# Power_driver_MCU.net
KiCad netlist of a schematic drawn in Altium Designer
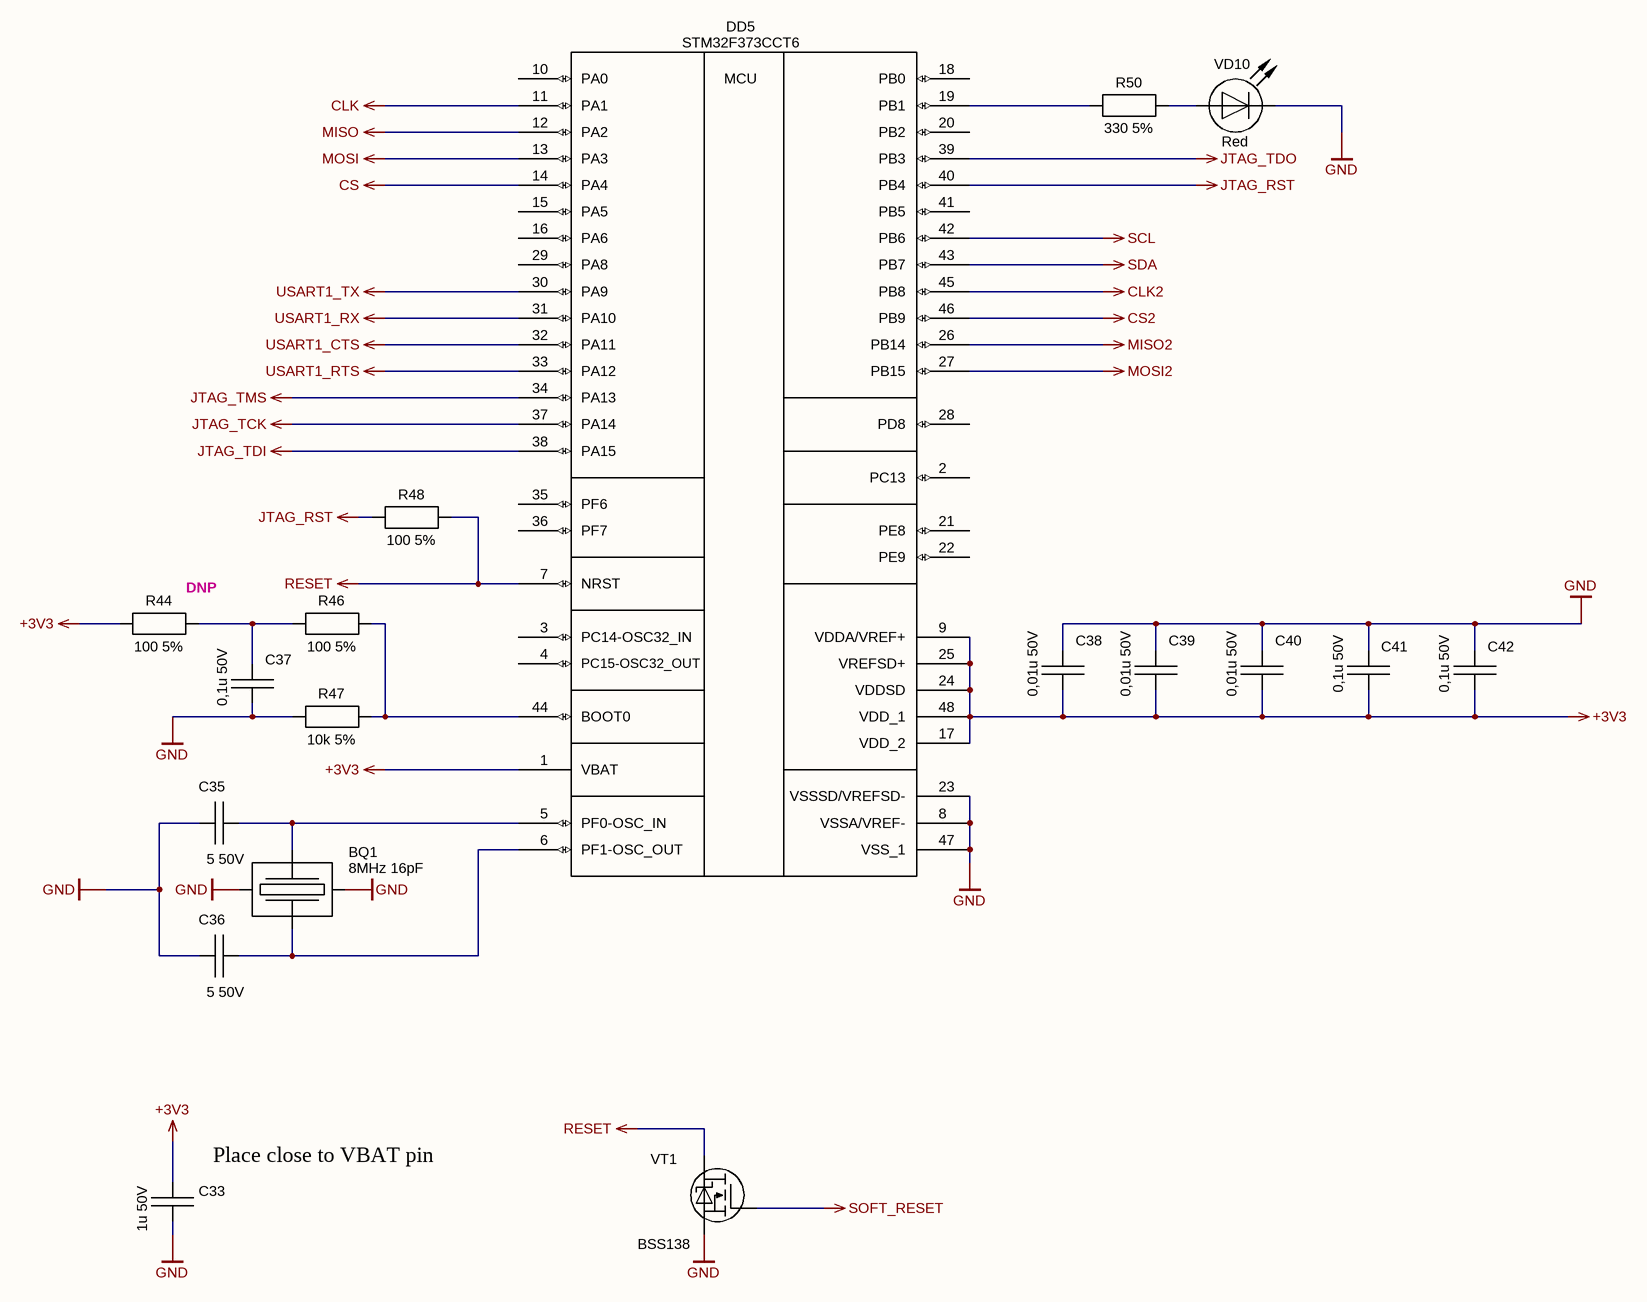
[diagram p0: Power_driver_MCU.SchDoc]

(export (version "E")
  (design (tool "Eeschema 10.0.6"))
  (components
    (comp (ref "BQ1")
      (value "8MHz 16pF")
      (footprint "Crystal_50x32x110")
      (description "Резонатор кварцевый 8 МГц, 50 ppm, 16 пФ, 5,0 x 3,2mm, SMT")
      (fields
        (field (name "PARTNUMBER") "KX-9A 8.0 MHz")
        (field (name "MANUFACTURER") "Geyer")
        (field (name "DESIGNER") "Pashinskiy")
      )
      (libsource (lib "RQCLib") (part "Crystal_4_pins"))
    )
    (comp (ref "C33")
      (value "1u 50V")
      (footprint "C0603_CAPC1608X09N")
      (description "Конденсатор керамический (MLCC) общего назначения 0603")
      (fields
        (field (name "PARTNUMBER") "CC0603KRX7R9BB105")
        (field (name "MANUFACTURER") "YAGEO")
        (field (name "DESIGNER") "Dudarev")
      )
      (libsource (lib "RQCLib") (part "Capacitor"))
    )
    (comp (ref "C35")
      (value "5 50V")
      (footprint "C0603_CAPC1608X09N")
      (description "Конденсатор керамический (MLCC) общего назначения 0603")
      (fields
        (field (name "PARTNUMBER") "CC0603CRNPO9BN5R0")
        (field (name "MANUFACTURER") "YAGEO")
        (field (name "DESIGNER") "Pashinskiy")
      )
      (libsource (lib "RQCLib") (part "Capacitor"))
    )
    (comp (ref "C36")
      (value "5 50V")
      (footprint "C0603_CAPC1608X09N")
      (description "Конденсатор керамический (MLCC) общего назначения 0603")
      (fields
        (field (name "PARTNUMBER") "CC0603CRNPO9BN5R0")
        (field (name "MANUFACTURER") "YAGEO")
        (field (name "DESIGNER") "Pashinskiy")
      )
      (libsource (lib "RQCLib") (part "Capacitor"))
    )
    (comp (ref "C37")
      (value "0,1u 50V")
      (footprint "C0603_CAPC1608X09N")
      (description "Конденсатор керамический (MLCC) общего назначения 0603")
      (fields
        (field (name "PARTNUMBER") "CC0603KRX7R9BB104")
        (field (name "MANUFACTURER") "YAGEO")
        (field (name "DESIGNER") "Dudarev")
      )
      (libsource (lib "RQCLib") (part "Capacitor"))
    )
    (comp (ref "C38")
      (value "0,01u 50V")
      (footprint "C0603_CAPC1608X09N")
      (description "Конденсатор керамический (MLCC) общего назначения 0603")
      (fields
        (field (name "PARTNUMBER") "CC0603KRX7R9BB103")
        (field (name "MANUFACTURER") "YAGEO")
        (field (name "DESIGNER") "Dudarev")
      )
      (libsource (lib "RQCLib") (part "Capacitor"))
    )
    (comp (ref "C39")
      (value "0,01u 50V")
      (footprint "C0603_CAPC1608X09N")
      (description "Конденсатор керамический (MLCC) общего назначения 0603")
      (fields
        (field (name "PARTNUMBER") "CC0603KRX7R9BB103")
        (field (name "MANUFACTURER") "YAGEO")
        (field (name "DESIGNER") "Dudarev")
      )
      (libsource (lib "RQCLib") (part "Capacitor"))
    )
    (comp (ref "C40")
      (value "0,01u 50V")
      (footprint "C0603_CAPC1608X09N")
      (description "Конденсатор керамический (MLCC) общего назначения 0603")
      (fields
        (field (name "PARTNUMBER") "CC0603KRX7R9BB103")
        (field (name "MANUFACTURER") "YAGEO")
        (field (name "DESIGNER") "Dudarev")
      )
      (libsource (lib "RQCLib") (part "Capacitor"))
    )
    (comp (ref "C41")
      (value "0,1u 50V")
      (footprint "C0603_CAPC1608X09N")
      (description "Конденсатор керамический (MLCC) общего назначения 0603")
      (fields
        (field (name "PARTNUMBER") "CC0603KRX7R9BB104")
        (field (name "MANUFACTURER") "YAGEO")
        (field (name "DESIGNER") "Dudarev")
      )
      (libsource (lib "RQCLib") (part "Capacitor"))
    )
    (comp (ref "C42")
      (value "0,1u 50V")
      (footprint "C0603_CAPC1608X09N")
      (description "Конденсатор керамический (MLCC) общего назначения 0603")
      (fields
        (field (name "PARTNUMBER") "CC0603KRX7R9BB104")
        (field (name "MANUFACTURER") "YAGEO")
        (field (name "DESIGNER") "Dudarev")
      )
      (libsource (lib "RQCLib") (part "Capacitor"))
    )
    (comp (ref "DD5")
      (value "STM32F373CCT6")
      (footprint "LQFP48_TSQFP50P900X900X160-48L")
      (description "Microcontroller ARM Cortex-M4, 32b, MCU+FPU, 1,25DMIPS, 256 kB Flash, 32kB SRAM, USB, LQFP48")
      (libsource (lib "IC_Controller") (part "STM32F373CCT6"))
    )
    (comp (ref "R44")
      (value "100 5%")
      (footprint "R0603_RESC1608X06N")
      (description "Резистор толстопленочный общего назначения 0603")
      (fields
        (field (name "PARTNUMBER") "RC0603JR-07100RL")
        (field (name "STAFF") "DNP")
        (field (name "MANUFACTURER") "YAGEO")
        (field (name "DESIGNER") "Dudarev")
      )
      (libsource (lib "RQCLib") (part "Resistor"))
    )
    (comp (ref "R46")
      (value "100 5%")
      (footprint "R0603_RESC1608X06N")
      (description "Резистор толстопленочный общего назначения 0603")
      (fields
        (field (name "PARTNUMBER") "RC0603JR-07100RL")
        (field (name "MANUFACTURER") "YAGEO")
        (field (name "DESIGNER") "Dudarev")
      )
      (libsource (lib "RQCLib") (part "Resistor"))
    )
    (comp (ref "R47")
      (value "10k 5%")
      (footprint "R0603_RESC1608X06N")
      (description "Резистор толстопленочный общего назначения 0603")
      (fields
        (field (name "PARTNUMBER") "RC0603JR-0710KL")
        (field (name "MANUFACTURER") "YAGEO")
        (field (name "DESIGNER") "Dudarev")
      )
      (libsource (lib "RQCLib") (part "Resistor"))
    )
    (comp (ref "R48")
      (value "100 5%")
      (footprint "R0603_RESC1608X06N")
      (description "Резистор толстопленочный общего назначения 0603")
      (fields
        (field (name "PARTNUMBER") "RC0603JR-07100RL")
        (field (name "MANUFACTURER") "YAGEO")
        (field (name "DESIGNER") "Dudarev")
      )
      (libsource (lib "RQCLib") (part "Resistor"))
    )
    (comp (ref "R50")
      (value "330 5%")
      (footprint "R0603_RESC1608X06N")
      (description "Резистор толстопленочный общего назначения 0603")
      (fields
        (field (name "PARTNUMBER") "RC0603JR-07330RL")
        (field (name "MANUFACTURER") "YAGEO")
        (field (name "DESIGNER") "Dudarev")
      )
      (libsource (lib "RQCLib") (part "Resistor"))
    )
    (comp (ref "VD10")
      (value "Red")
      (footprint "LED_0603")
      (description "LED SMD Super Red 1,6mm x 0,8mm")
      (fields
        (field (name "PARTNUMBER") "VLMS1300-GS08")
        (field (name "MANUFACTURER") "Vishay Semiconductors")
        (field (name "DESIGNER") "Losev")
      )
      (libsource (lib "RQCLib") (part "LED"))
    )
    (comp (ref "VT1")
      (value "BSS138")
      (footprint "SOT23_SOT95P237X110-3M")
      (description "N-Channel MOSFET transistor Logic level")
      (libsource (lib "Discrete") (part "N-MOSFET"))
    )
  )
  (nets
    (net (code "1") (name "+3V3") (class "Default")
      (node (ref "C33") (pin "2") (pinfunction "2_2") (pintype "passive"))
      (node (ref "C38") (pin "2") (pinfunction "2_2") (pintype "passive"))
      (node (ref "C39") (pin "2") (pinfunction "2_2") (pintype "passive"))
      (node (ref "C40") (pin "2") (pinfunction "2_2") (pintype "passive"))
      (node (ref "C41") (pin "2") (pinfunction "2_2") (pintype "passive"))
      (node (ref "C42") (pin "2") (pinfunction "2_2") (pintype "passive"))
      (node (ref "DD5") (pin "1") (pinfunction "VBAT_1") (pintype "power_in"))
      (node (ref "DD5") (pin "17") (pinfunction "VDD_2_17") (pintype "power_in"))
      (node (ref "DD5") (pin "24") (pinfunction "VDDSD_24") (pintype "power_in"))
      (node (ref "DD5") (pin "25") (pinfunction "VREFSD+_25") (pintype "power_in"))
      (node (ref "DD5") (pin "48") (pinfunction "VDD_1_48") (pintype "power_in"))
      (node (ref "DD5") (pin "9") (pinfunction "VDDA/VREF+_9") (pintype "power_in"))
      (node (ref "R44") (pin "1") (pinfunction "1_1") (pintype "passive"))
    )
    (net (code "2") (name "CLK") (class "Default")
      (node (ref "DD5") (pin "11") (pinfunction "PA1_11") (pintype "bidirectional"))
    )
    (net (code "3") (name "CLK2") (class "Default")
      (node (ref "DD5") (pin "45") (pinfunction "PB8_45") (pintype "bidirectional"))
    )
    (net (code "4") (name "CS") (class "Default")
      (node (ref "DD5") (pin "14") (pinfunction "PA4_14") (pintype "bidirectional"))
    )
    (net (code "5") (name "CS2") (class "Default")
      (node (ref "DD5") (pin "46") (pinfunction "PB9_46") (pintype "bidirectional"))
    )
    (net (code "6") (name "GND") (class "Default")
      (node (ref "BQ1") (pin "2") (pinfunction "2_2") (pintype "passive"))
      (node (ref "BQ1") (pin "4") (pinfunction "4_4") (pintype "passive"))
      (node (ref "C33") (pin "1") (pinfunction "1_1") (pintype "passive"))
      (node (ref "C35") (pin "1") (pinfunction "1_1") (pintype "passive"))
      (node (ref "C36") (pin "1") (pinfunction "1_1") (pintype "passive"))
      (node (ref "C37") (pin "2") (pinfunction "2_2") (pintype "passive"))
      (node (ref "C38") (pin "1") (pinfunction "1_1") (pintype "passive"))
      (node (ref "C39") (pin "1") (pinfunction "1_1") (pintype "passive"))
      (node (ref "C40") (pin "1") (pinfunction "1_1") (pintype "passive"))
      (node (ref "C41") (pin "1") (pinfunction "1_1") (pintype "passive"))
      (node (ref "C42") (pin "1") (pinfunction "1_1") (pintype "passive"))
      (node (ref "DD5") (pin "23") (pinfunction "VSSSD/VREFSD-_23") (pintype "power_in"))
      (node (ref "DD5") (pin "47") (pinfunction "VSS_1_47") (pintype "power_in"))
      (node (ref "DD5") (pin "8") (pinfunction "VSSA/VREF-_8") (pintype "power_in"))
      (node (ref "R47") (pin "1") (pinfunction "1_1") (pintype "passive"))
      (node (ref "VD10") (pin "1") (pinfunction "K_1") (pintype "passive"))
      (node (ref "VT1") (pin "2") (pinfunction "S_2") (pintype "passive"))
    )
    (net (code "7") (name "JTAG_RST") (class "Default")
      (node (ref "DD5") (pin "40") (pinfunction "PB4_40") (pintype "bidirectional"))
      (node (ref "R48") (pin "1") (pinfunction "1_1") (pintype "passive"))
    )
    (net (code "8") (name "JTAG_TCK") (class "Default")
      (node (ref "DD5") (pin "37") (pinfunction "PA14_37") (pintype "bidirectional"))
    )
    (net (code "9") (name "JTAG_TDI") (class "Default")
      (node (ref "DD5") (pin "38") (pinfunction "PA15_38") (pintype "bidirectional"))
    )
    (net (code "10") (name "JTAG_TDO") (class "Default")
      (node (ref "DD5") (pin "39") (pinfunction "PB3_39") (pintype "bidirectional"))
    )
    (net (code "11") (name "JTAG_TMS") (class "Default")
      (node (ref "DD5") (pin "34") (pinfunction "PA13_34") (pintype "bidirectional"))
    )
    (net (code "12") (name "MISO") (class "Default")
      (node (ref "DD5") (pin "12") (pinfunction "PA2_12") (pintype "bidirectional"))
    )
    (net (code "13") (name "MISO2") (class "Default")
      (node (ref "DD5") (pin "26") (pinfunction "PB14_26") (pintype "bidirectional"))
    )
    (net (code "14") (name "MOSI") (class "Default")
      (node (ref "DD5") (pin "13") (pinfunction "PA3_13") (pintype "bidirectional"))
    )
    (net (code "15") (name "MOSI2") (class "Default")
      (node (ref "DD5") (pin "27") (pinfunction "PB15_27") (pintype "bidirectional"))
    )
    (net (code "16") (name "Net-(C37-Pad1)") (class "Default")
      (node (ref "C37") (pin "1") (pinfunction "1_1") (pintype "passive"))
      (node (ref "R44") (pin "2") (pinfunction "2_2") (pintype "passive"))
      (node (ref "R46") (pin "1") (pinfunction "1_1") (pintype "passive"))
    )
    (net (code "17") (name "Net-(DD5-BOOT0)") (class "Default")
      (node (ref "DD5") (pin "44") (pinfunction "BOOT0_44") (pintype "bidirectional"))
      (node (ref "R46") (pin "2") (pinfunction "2_2") (pintype "passive"))
      (node (ref "R47") (pin "2") (pinfunction "2_2") (pintype "passive"))
    )
    (net (code "18") (name "Net-(DD5-PB1)") (class "Default")
      (node (ref "DD5") (pin "19") (pinfunction "PB1_19") (pintype "bidirectional"))
      (node (ref "R50") (pin "1") (pinfunction "1_1") (pintype "passive"))
    )
    (net (code "19") (name "Net-(DD5-PF0-OSC_IN)") (class "Default")
      (node (ref "BQ1") (pin "3") (pinfunction "3_3") (pintype "passive"))
      (node (ref "C35") (pin "2") (pinfunction "2_2") (pintype "passive"))
      (node (ref "DD5") (pin "5") (pinfunction "PF0-OSC_IN_5") (pintype "bidirectional"))
    )
    (net (code "20") (name "Net-(DD5-PF1-OSC_OUT)") (class "Default")
      (node (ref "BQ1") (pin "1") (pinfunction "1_1") (pintype "passive"))
      (node (ref "C36") (pin "2") (pinfunction "2_2") (pintype "passive"))
      (node (ref "DD5") (pin "6") (pinfunction "PF1-OSC_OUT_6") (pintype "bidirectional"))
    )
    (net (code "21") (name "Net-(VD10-A)") (class "Default")
      (node (ref "R50") (pin "2") (pinfunction "2_2") (pintype "passive"))
      (node (ref "VD10") (pin "2") (pinfunction "A_2") (pintype "passive"))
    )
    (net (code "22") (name "RESET") (class "Default")
      (node (ref "DD5") (pin "7") (pinfunction "NRST_7") (pintype "bidirectional"))
      (node (ref "R48") (pin "2") (pinfunction "2_2") (pintype "passive"))
      (node (ref "VT1") (pin "3") (pinfunction "D_3") (pintype "passive"))
    )
    (net (code "23") (name "SCL") (class "Default")
      (node (ref "DD5") (pin "42") (pinfunction "PB6_42") (pintype "bidirectional"))
    )
    (net (code "24") (name "SDA") (class "Default")
      (node (ref "DD5") (pin "43") (pinfunction "PB7_43") (pintype "bidirectional"))
    )
    (net (code "25") (name "SOFT_RESET") (class "Default")
      (node (ref "VT1") (pin "1") (pinfunction "G_1") (pintype "passive"))
    )
    (net (code "26") (name "USART1_CTS") (class "Default")
      (node (ref "DD5") (pin "32") (pinfunction "PA11_32") (pintype "bidirectional"))
    )
    (net (code "27") (name "USART1_RTS") (class "Default")
      (node (ref "DD5") (pin "33") (pinfunction "PA12_33") (pintype "bidirectional"))
    )
    (net (code "28") (name "USART1_RX") (class "Default")
      (node (ref "DD5") (pin "31") (pinfunction "PA10_31") (pintype "bidirectional"))
    )
    (net (code "29") (name "USART1_TX") (class "Default")
      (node (ref "DD5") (pin "30") (pinfunction "PA9_30") (pintype "bidirectional"))
    )
    (net (code "30") (name "unconnected-(DD5-PA0-Pad10)") (class "Default")
      (node (ref "DD5") (pin "10") (pinfunction "PA0_10") (pintype "bidirectional"))
    )
    (net (code "31") (name "unconnected-(DD5-PA5-Pad15)") (class "Default")
      (node (ref "DD5") (pin "15") (pinfunction "PA5_15") (pintype "bidirectional"))
    )
    (net (code "32") (name "unconnected-(DD5-PA6-Pad16)") (class "Default")
      (node (ref "DD5") (pin "16") (pinfunction "PA6_16") (pintype "bidirectional"))
    )
    (net (code "33") (name "unconnected-(DD5-PA8-Pad29)") (class "Default")
      (node (ref "DD5") (pin "29") (pinfunction "PA8_29") (pintype "bidirectional"))
    )
    (net (code "34") (name "unconnected-(DD5-PB0-Pad18)") (class "Default")
      (node (ref "DD5") (pin "18") (pinfunction "PB0_18") (pintype "bidirectional"))
    )
    (net (code "35") (name "unconnected-(DD5-PB2-Pad20)") (class "Default")
      (node (ref "DD5") (pin "20") (pinfunction "PB2_20") (pintype "bidirectional"))
    )
    (net (code "36") (name "unconnected-(DD5-PB5-Pad41)") (class "Default")
      (node (ref "DD5") (pin "41") (pinfunction "PB5_41") (pintype "bidirectional"))
    )
    (net (code "37") (name "unconnected-(DD5-PC13-Pad2)") (class "Default")
      (node (ref "DD5") (pin "2") (pinfunction "PC13_2") (pintype "bidirectional"))
    )
    (net (code "38") (name "unconnected-(DD5-PC14-OSC32_IN-Pad3)") (class "Default")
      (node (ref "DD5") (pin "3") (pinfunction "PC14-OSC32_IN_3") (pintype "bidirectional"))
    )
    (net (code "39") (name "unconnected-(DD5-PC15-OSC32_OUT-Pad4)") (class "Default")
      (node (ref "DD5") (pin "4") (pinfunction "PC15-OSC32_OUT_4") (pintype "bidirectional"))
    )
    (net (code "40") (name "unconnected-(DD5-PD8-Pad28)") (class "Default")
      (node (ref "DD5") (pin "28") (pinfunction "PD8_28") (pintype "bidirectional"))
    )
    (net (code "41") (name "unconnected-(DD5-PE8-Pad21)") (class "Default")
      (node (ref "DD5") (pin "21") (pinfunction "PE8_21") (pintype "bidirectional"))
    )
    (net (code "42") (name "unconnected-(DD5-PE9-Pad22)") (class "Default")
      (node (ref "DD5") (pin "22") (pinfunction "PE9_22") (pintype "bidirectional"))
    )
    (net (code "43") (name "unconnected-(DD5-PF6-Pad35)") (class "Default")
      (node (ref "DD5") (pin "35") (pinfunction "PF6_35") (pintype "bidirectional"))
    )
    (net (code "44") (name "unconnected-(DD5-PF7-Pad36)") (class "Default")
      (node (ref "DD5") (pin "36") (pinfunction "PF7_36") (pintype "bidirectional"))
    )
  )
)
